# Power.net
KiCad netlist of a schematic drawn in Altium Designer
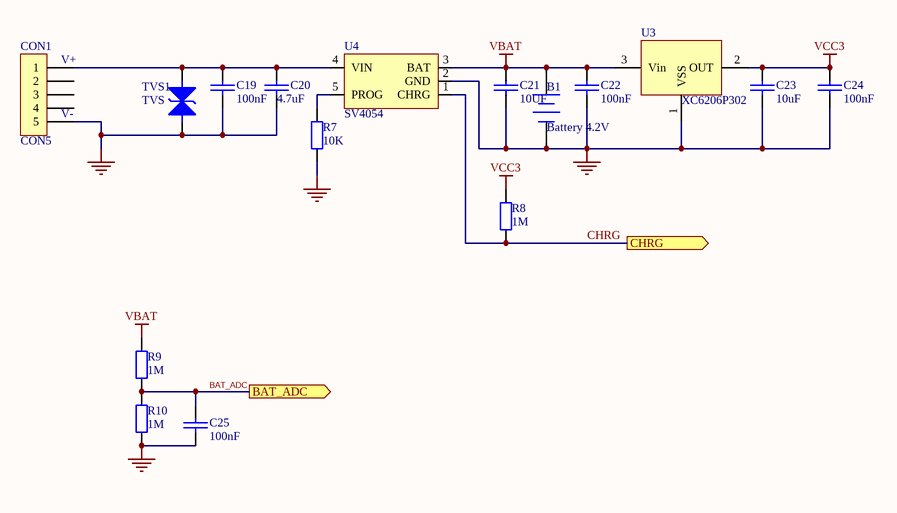
[diagram p0: Power.SchDoc]

(export (version "E")
  (design (tool "Eeschema 10.0.6"))
  (components
    (comp (ref "B1")
      (value "Battery 4.2V")
      (footprint "JP2S")
      (description "Multicell Battery")
      (fields (field (name "PUBLISHER") "Altium Limited"))
      (libsource (lib "*") (part "Battery"))
    )
    (comp (ref "C19")
      (value "100nF")
      (footprint "0603")
      (description "Capacitor")
      (libsource (lib "*") (part "CAP"))
    )
    (comp (ref "C20")
      (value "4.7uF")
      (footprint "0603")
      (description "Capacitor")
      (libsource (lib "*") (part "CAP"))
    )
    (comp (ref "C21")
      (value "10UF")
      (footprint "0603")
      (description "Capacitor")
      (libsource (lib "*") (part "CAP"))
    )
    (comp (ref "C22")
      (value "100nF")
      (footprint "0603")
      (description "Capacitor")
      (libsource (lib "*") (part "CAP"))
    )
    (comp (ref "C23")
      (value "10uF")
      (footprint "0603")
      (description "Capacitor")
      (libsource (lib "*") (part "CAP"))
    )
    (comp (ref "C24")
      (value "100nF")
      (footprint "0603")
      (description "Capacitor")
      (libsource (lib "*") (part "CAP"))
    )
    (comp (ref "C25") (value "100nF") (description "Capacitor") (libsource (lib "*") (part "CAP")))
    (comp (ref "CON1") (value "CON5") (description "Connector") (libsource (lib "*") (part "CON5")))
    (comp (ref "R7")
      (value "10K")
      (footprint "AXIAL-0.4")
      (description "1%@100mA")
      (fields (field (name "PUBLISHER") "Altium Limited"))
      (libsource (lib "Miscellaneous Devices") (part "Res2"))
    )
    (comp (ref "R8")
      (value "1M")
      (fields (field (name "PUBLISHER") "Altium Limited"))
      (libsource (lib "Miscellaneous Devices") (part "Res2"))
    )
    (comp (ref "R9")
      (value "1M")
      (fields (field (name "PUBLISHER") "Altium Limited"))
      (libsource (lib "Miscellaneous Devices") (part "Res2"))
    )
    (comp (ref "R10")
      (value "1M")
      (fields (field (name "PUBLISHER") "Altium Limited"))
      (libsource (lib "Miscellaneous Devices") (part "Res2"))
    )
    (comp (ref "TVS1") (value "TVS") (footprint "SOD-123") (libsource (lib "*") (part "TVS")))
    (comp (ref "U3") (value "XC6206P302") (footprint "SOT-23") (libsource (lib "*") (part "XC6206P302")))
    (comp (ref "U4") (value "SV4054") (footprint "SOT-25") (libsource (lib "*") (part "SV4054")))
  )
  (nets
    (net (code "1") (name "/BAT_ADC") (class "Default")
      (node (ref "C25") (pin "2") (pinfunction "2_2") (pintype "passive"))
      (node (ref "R10") (pin "2") (pinfunction "2_2") (pintype "passive"))
      (node (ref "R9") (pin "1") (pinfunction "1_1") (pintype "passive"))
    )
    (net (code "2") (name "/CHRG") (class "Default")
      (node (ref "R8") (pin "1") (pinfunction "1_1") (pintype "passive"))
      (node (ref "U4") (pin "1") (pinfunction "CHRG_1") (pintype "passive"))
    )
    (net (code "3") (name "GND") (class "Default")
      (node (ref "B1") (pin "2") (pinfunction "-_2") (pintype "passive"))
      (node (ref "C19") (pin "1") (pinfunction "1_1") (pintype "passive"))
      (node (ref "C20") (pin "1") (pinfunction "1_1") (pintype "passive"))
      (node (ref "C21") (pin "1") (pinfunction "1_1") (pintype "passive"))
      (node (ref "C22") (pin "1") (pinfunction "1_1") (pintype "passive"))
      (node (ref "C23") (pin "1") (pinfunction "1_1") (pintype "passive"))
      (node (ref "C24") (pin "1") (pinfunction "1_1") (pintype "passive"))
      (node (ref "C25") (pin "1") (pinfunction "1_1") (pintype "passive"))
      (node (ref "CON1") (pin "5") (pinfunction "5_5") (pintype "passive"))
      (node (ref "R10") (pin "1") (pinfunction "1_1") (pintype "passive"))
      (node (ref "R7") (pin "1") (pinfunction "1_1") (pintype "passive"))
      (node (ref "TVS1") (pin "1") (pinfunction "1_1") (pintype "passive"))
      (node (ref "U3") (pin "1") (pinfunction "VSS_1") (pintype "passive"))
      (node (ref "U4") (pin "2") (pinfunction "GND_2") (pintype "passive"))
    )
    (net (code "4") (name "Net-(U4-PROG)") (class "Default")
      (node (ref "R7") (pin "2") (pinfunction "2_2") (pintype "passive"))
      (node (ref "U4") (pin "5") (pinfunction "PROG_5") (pintype "passive"))
    )
    (net (code "5") (name "Net-(U4-VIN)") (class "Default")
      (node (ref "C19") (pin "2") (pinfunction "2_2") (pintype "passive"))
      (node (ref "C20") (pin "2") (pinfunction "2_2") (pintype "passive"))
      (node (ref "CON1") (pin "1") (pinfunction "1_1") (pintype "passive"))
      (node (ref "TVS1") (pin "2") (pinfunction "2_2") (pintype "passive"))
      (node (ref "U4") (pin "4") (pinfunction "VIN_4") (pintype "passive"))
    )
    (net (code "6") (name "VBAT") (class "Default")
      (node (ref "B1") (pin "1") (pinfunction "+_1") (pintype "passive"))
      (node (ref "C21") (pin "2") (pinfunction "2_2") (pintype "passive"))
      (node (ref "C22") (pin "2") (pinfunction "2_2") (pintype "passive"))
      (node (ref "R9") (pin "2") (pinfunction "2_2") (pintype "passive"))
      (node (ref "U3") (pin "3") (pinfunction "Vin_3") (pintype "passive"))
      (node (ref "U4") (pin "3") (pinfunction "BAT_3") (pintype "passive"))
    )
    (net (code "7") (name "VCC3") (class "Default")
      (node (ref "C23") (pin "2") (pinfunction "2_2") (pintype "passive"))
      (node (ref "C24") (pin "2") (pinfunction "2_2") (pintype "passive"))
      (node (ref "R8") (pin "2") (pinfunction "2_2") (pintype "passive"))
      (node (ref "U3") (pin "2") (pinfunction "OUT_2") (pintype "passive"))
    )
    (net (code "8") (name "unconnected-(CON1-Pad2)") (class "Default")
      (node (ref "CON1") (pin "2") (pinfunction "2_2") (pintype "passive"))
    )
    (net (code "9") (name "unconnected-(CON1-Pad3)") (class "Default")
      (node (ref "CON1") (pin "3") (pinfunction "3_3") (pintype "passive"))
    )
    (net (code "10") (name "unconnected-(CON1-Pad4)") (class "Default")
      (node (ref "CON1") (pin "4") (pinfunction "4_4") (pintype "passive"))
    )
  )
)
